# isolation-alt.net
KiCad netlist of a schematic drawn in Altium Designer
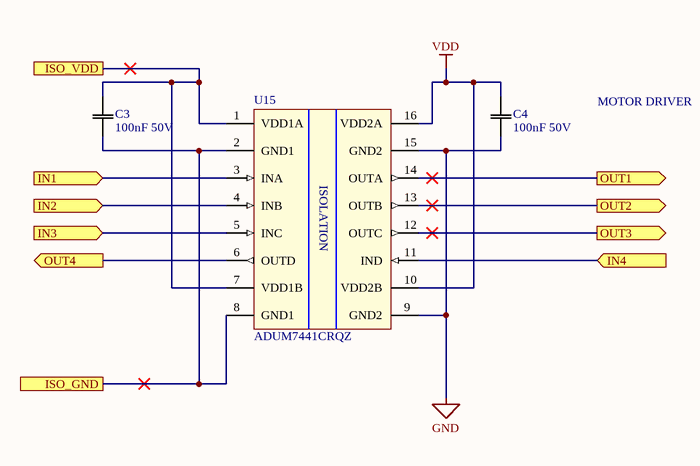
[diagram p0: isolation-alt.SchDoc]

(export (version "E")
  (design (tool "Eeschema 10.0.6"))
  (components
    (comp (ref "C3")
      (value "100nF 50V")
      (footprint "0603")
      (description "Default Symbol for Capacitors")
      (fields (field (name "PART NUMBER") "CAP 100nF 50V") (field (name "TOLERANCE") "10%"))
      (libsource (lib "capacitor_library") (part "CAP_Default"))
    )
    (comp (ref "C4")
      (value "100nF 50V")
      (footprint "0603")
      (description "Default Symbol for Capacitors")
      (fields (field (name "PART NUMBER") "CAP 100nF 50V") (field (name "TOLERANCE") "10%"))
      (libsource (lib "capacitor_library") (part "CAP_Default"))
    )
    (comp (ref "U15")
      (value "ADUM7441CRQZ")
      (footprint "SOP64P600X175-16N")
      (description "Digital Isolator CMOS 4-CH 150Mbps 16-Pin QSOP T/R")
      (fields (field (name "PART NUMBER") "ISO ADUM7441CRQZ"))
      (libsource (lib "IC_Library") (part "ISO ADUM7441CRQZ"))
    )
  )
  (nets
    (net (code "1") (name "/IN1") (class "Default")
      (node (ref "U15") (pin "3") (pinfunction "INA_3") (pintype "input"))
    )
    (net (code "2") (name "/IN2") (class "Default")
      (node (ref "U15") (pin "4") (pinfunction "INB_4") (pintype "input"))
    )
    (net (code "3") (name "/IN3") (class "Default")
      (node (ref "U15") (pin "5") (pinfunction "INC_5") (pintype "input"))
    )
    (net (code "4") (name "/IN4") (class "Default")
      (node (ref "U15") (pin "11") (pinfunction "IND_11") (pintype "input"))
    )
    (net (code "5") (name "/ISO_GND") (class "Default")
      (node (ref "C3") (pin "1") (pinfunction "C1_1") (pintype "passive"))
      (node (ref "U15") (pin "2") (pinfunction "GND1_2") (pintype "power_in"))
      (node (ref "U15") (pin "8") (pinfunction "GND1_8") (pintype "power_in"))
    )
    (net (code "6") (name "/ISO_VDD") (class "Default")
      (node (ref "C3") (pin "2") (pinfunction "C2_2") (pintype "passive"))
      (node (ref "U15") (pin "1") (pinfunction "VDD1A_1") (pintype "power_in"))
      (node (ref "U15") (pin "7") (pinfunction "VDD1B_7") (pintype "passive"))
    )
    (net (code "7") (name "/OUT1") (class "Default")
      (node (ref "U15") (pin "14") (pinfunction "OUTA_14") (pintype "output"))
    )
    (net (code "8") (name "/OUT2") (class "Default")
      (node (ref "U15") (pin "13") (pinfunction "OUTB_13") (pintype "output"))
    )
    (net (code "9") (name "/OUT3") (class "Default")
      (node (ref "U15") (pin "12") (pinfunction "OUTC_12") (pintype "output"))
    )
    (net (code "10") (name "/OUT4") (class "Default")
      (node (ref "U15") (pin "6") (pinfunction "OUTD_6") (pintype "output"))
    )
    (net (code "11") (name "GND") (class "Default")
      (node (ref "C4") (pin "1") (pinfunction "C1_1") (pintype "passive"))
      (node (ref "U15") (pin "15") (pinfunction "GND2_15") (pintype "power_in"))
      (node (ref "U15") (pin "9") (pinfunction "GND2_9") (pintype "power_in"))
    )
    (net (code "12") (name "VDD") (class "Default")
      (node (ref "C4") (pin "2") (pinfunction "C2_2") (pintype "passive"))
      (node (ref "U15") (pin "10") (pinfunction "VDD2B_10") (pintype "passive"))
      (node (ref "U15") (pin "16") (pinfunction "VDD2A_16") (pintype "power_in"))
    )
  )
)
